# CPU.net
KiCad netlist of a schematic drawn in Altium Designer
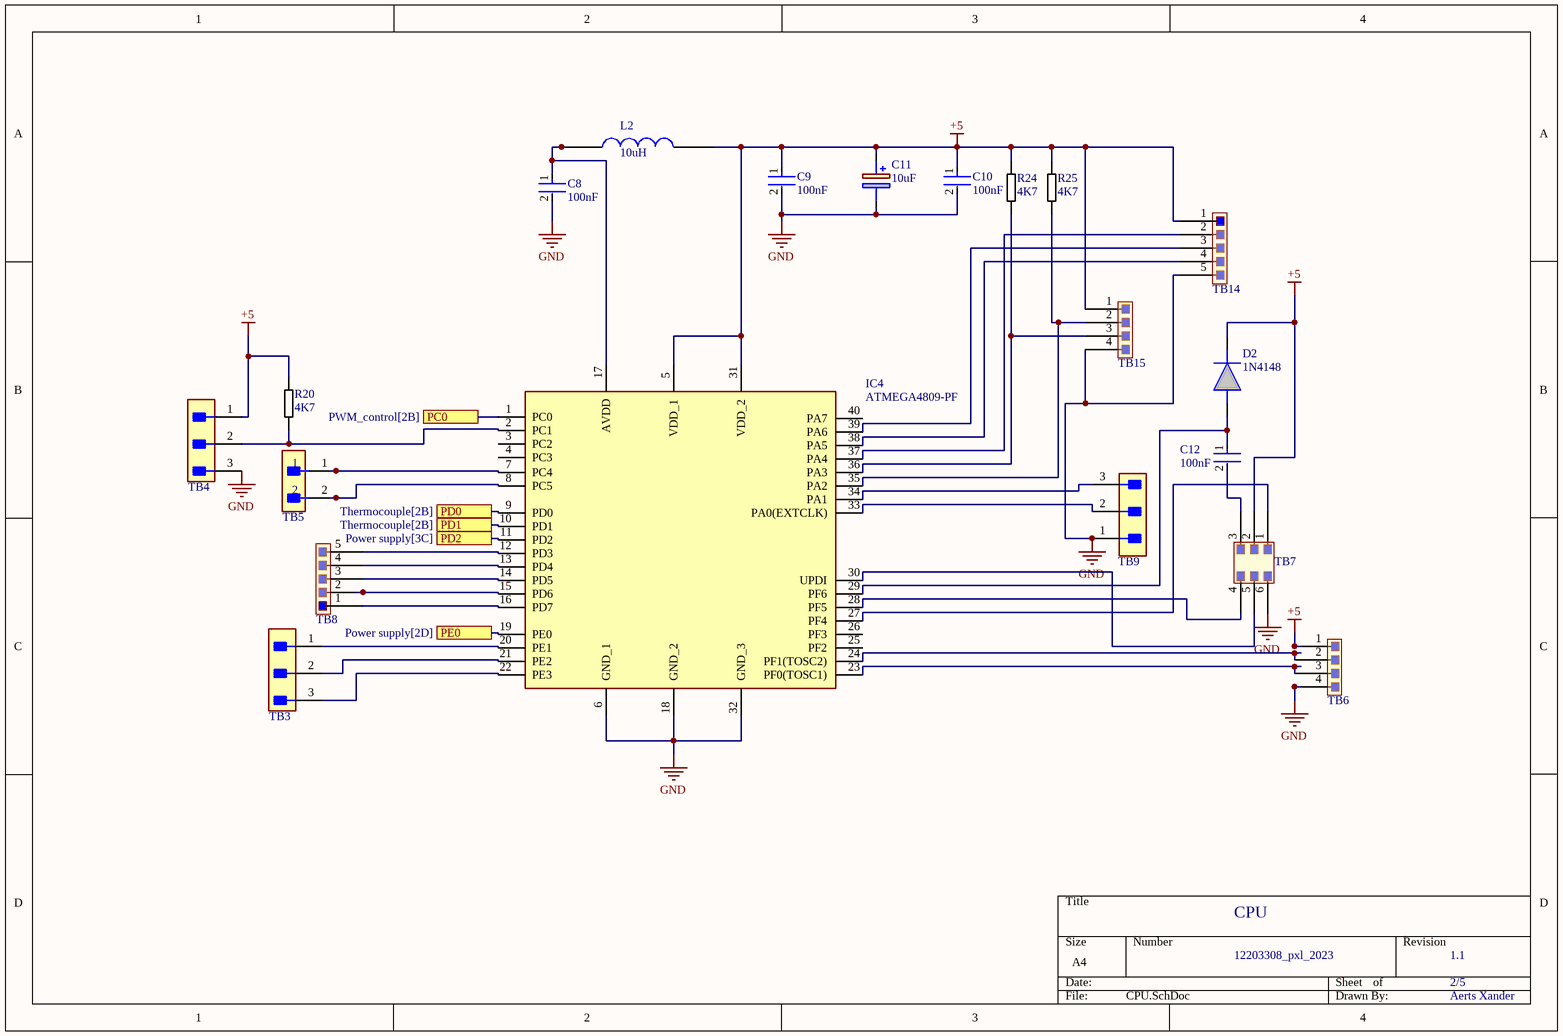
[diagram p0: CPU.SchDoc]

(export (version "E")
  (design (tool "Eeschema 10.0.6"))
  (components
    (comp (ref "C8")
      (value "100nF")
      (footprint "0805")
      (description "CAP CER 10000PF 50V X7R 0603")
      (fields (field (name "TOLERANCE") "0.1") (field (name "MANUFACTURER PART NUMBER") "CC0603KRX7R9BB103"))
      (libsource (lib "soldeerstation") (part "Capacitor 0805"))
    )
    (comp (ref "C9")
      (value "100nF")
      (footprint "0805")
      (description "CAP CER 10000PF 50V X7R 0603")
      (fields (field (name "TOLERANCE") "0.1") (field (name "MANUFACTURER PART NUMBER") "CC0603KRX7R9BB103"))
      (libsource (lib "soldeerstation") (part "Capacitor 0805"))
    )
    (comp (ref "C10")
      (value "100nF")
      (footprint "0805")
      (description "CAP CER 10000PF 50V X7R 0603")
      (fields (field (name "TOLERANCE") "0.1") (field (name "MANUFACTURER PART NUMBER") "CC0603KRX7R9BB103"))
      (libsource (lib "soldeerstation") (part "Capacitor 0805"))
    )
    (comp (ref "C11")
      (value "10uF")
      (footprint "10uF tht")
      (libsource (lib "soldeerstation") (part "10uF tht"))
    )
    (comp (ref "C12")
      (value "100nF")
      (footprint "0805")
      (description "CAP CER 10000PF 50V X7R 0603")
      (fields (field (name "TOLERANCE") "0.1") (field (name "MANUFACTURER PART NUMBER") "CC0603KRX7R9BB103"))
      (libsource (lib "soldeerstation") (part "Capacitor 0805"))
    )
    (comp (ref "D2")
      (value "1N4148")
      (footprint "1n4148")
      (description "Small Signal Diode, 100V 0.3A 2-Pin DO35")
      (fields (field (name "MOUSER PART NUMBER") "512-1N4148"))
      (libsource (lib "soldeerstation") (part "1N4148"))
    )
    (comp (ref "IC4")
      (value "ATMEGA4809-PF")
      (footprint "ATMEGA4809-PF")
      (description "Integrated Circuit")
      (fields (field (name "MOUSER PART NUMBER") "556-ATMEGA4809-PF"))
      (libsource (lib "soldeerstation") (part "ATMEGA4809-PF"))
    )
    (comp (ref "L2")
      (value "10uH")
      (footprint "10uH tht")
      (libsource (lib "soldeerstation") (part "10uH tht"))
    )
    (comp (ref "R20")
      (value "4K7")
      (footprint "0805")
      (fields (field (name "MANUFACTURER") "Vishay Dale") (field (name "PART NUMBER") "CRCW08050000Z0EA"))
      (libsource (lib "soldeerstation") (part "resistor"))
    )
    (comp (ref "R24")
      (value "4K7")
      (footprint "0805")
      (fields (field (name "MANUFACTURER") "Vishay Dale") (field (name "PART NUMBER") "CRCW08050000Z0EA"))
      (libsource (lib "soldeerstation") (part "resistor"))
    )
    (comp (ref "R25")
      (value "4K7")
      (footprint "0805")
      (fields (field (name "MANUFACTURER") "Vishay Dale") (field (name "PART NUMBER") "CRCW08050000Z0EA"))
      (libsource (lib "soldeerstation") (part "resistor"))
    )
    (comp (ref "TB3")
      (value "87224-3")
      (footprint "3x1 header tht")
      (description "CONN HEADER VERT 3POS 2.54MM")
      (libsource (lib "") (part "3x1 header tht_1"))
    )
    (comp (ref "TB4")
      (value "87224-3")
      (footprint "3x1 header tht")
      (description "CONN HEADER VERT 3POS 2.54MM")
      (libsource (lib "") (part "3x1 header tht_1"))
    )
    (comp (ref "TB5")
      (value "TSW-102-07-L-S")
      (footprint "2x1 header tht")
      (description "CONN HEADER VERT 2POS 2.54MM")
      (libsource (lib "soldeerstation") (part "2x1 header tht"))
    )
    (comp (ref "TB6")
      (value "4x1 header tht")
      (footprint "4x1 header tht")
      (libsource (lib "soldeerstation") (part "4x1 header tht"))
    )
    (comp (ref "TB7")
      (value "6x2 header tht")
      (footprint "6x2 header tht")
      (libsource (lib "soldeerstation") (part "6x2 header tht"))
    )
    (comp (ref "TB8")
      (value "5x1 header tht")
      (footprint "5x1 header tht")
      (libsource (lib "") (part "5x1 header tht_1"))
    )
    (comp (ref "TB9")
      (value "87224-3")
      (footprint "3x1 header tht")
      (description "CONN HEADER VERT 3POS 2.54MM")
      (libsource (lib "soldeerstation") (part "3x1 header tht"))
    )
    (comp (ref "TB14")
      (value "5x1 header tht")
      (footprint "5x1 header tht")
      (libsource (lib "soldeerstation") (part "5x1 header tht"))
    )
    (comp (ref "TB15")
      (value "4x1 header tht")
      (footprint "4x1 header tht")
      (libsource (lib "soldeerstation") (part "4x1 header tht"))
    )
  )
  (nets
    (net (code "1") (name "+5") (class "Default")
      (node (ref "C10") (pin "1") (pinfunction "1_1") (pintype "passive"))
      (node (ref "C11") (pin "1") (pinfunction "+_1") (pintype "passive"))
      (node (ref "C9") (pin "1") (pinfunction "1_1") (pintype "passive"))
      (node (ref "D2") (pin "1") (pinfunction "K_1") (pintype "passive"))
      (node (ref "IC4") (pin "31") (pinfunction "VDD_2_31") (pintype "passive"))
      (node (ref "IC4") (pin "5") (pinfunction "VDD_1_5") (pintype "passive"))
      (node (ref "L2") (pin "2") (pinfunction "32_2") (pintype "passive"))
      (node (ref "R20") (pin "2") (pinfunction "2_2") (pintype "passive"))
      (node (ref "R24") (pin "2") (pinfunction "2_2") (pintype "passive"))
      (node (ref "R25") (pin "2") (pinfunction "2_2") (pintype "passive"))
      (node (ref "TB14") (pin "1") (pinfunction "20_1") (pintype "passive"))
      (node (ref "TB15") (pin "1") (pinfunction "16_1") (pintype "passive"))
      (node (ref "TB4") (pin "1") (pinfunction "1_1") (pintype "passive"))
      (node (ref "TB6") (pin "1") (pinfunction "16_1") (pintype "passive"))
      (node (ref "TB7") (pin "2") (pinfunction "22_2") (pintype "passive"))
    )
    (net (code "2") (name "/PC0") (class "Default")
      (node (ref "IC4") (pin "1") (pinfunction "PC0_1") (pintype "passive"))
    )
    (net (code "3") (name "/PD0") (class "Default")
      (node (ref "IC4") (pin "9") (pinfunction "PD0_9") (pintype "passive"))
    )
    (net (code "4") (name "/PD1") (class "Default")
      (node (ref "IC4") (pin "10") (pinfunction "PD1_10") (pintype "passive"))
    )
    (net (code "5") (name "/PD2") (class "Default")
      (node (ref "IC4") (pin "11") (pinfunction "PD2_11") (pintype "passive"))
    )
    (net (code "6") (name "/PE0") (class "Default")
      (node (ref "IC4") (pin "19") (pinfunction "PE0_19") (pintype "passive"))
    )
    (net (code "7") (name "GND") (class "Default")
      (node (ref "C10") (pin "2") (pinfunction "2_2") (pintype "passive"))
      (node (ref "C11") (pin "2") (pinfunction "-_2") (pintype "passive"))
      (node (ref "C8") (pin "2") (pinfunction "2_2") (pintype "passive"))
      (node (ref "C9") (pin "2") (pinfunction "2_2") (pintype "passive"))
      (node (ref "IC4") (pin "18") (pinfunction "GND_2_18") (pintype "passive"))
      (node (ref "IC4") (pin "32") (pinfunction "GND_3_32") (pintype "passive"))
      (node (ref "IC4") (pin "6") (pinfunction "GND_1_6") (pintype "passive"))
      (node (ref "TB14") (pin "5") (pinfunction "19_5") (pintype "passive"))
      (node (ref "TB15") (pin "4") (pinfunction "19_4") (pintype "passive"))
      (node (ref "TB4") (pin "3") (pinfunction "3_3") (pintype "passive"))
      (node (ref "TB6") (pin "4") (pinfunction "19_4") (pintype "passive"))
      (node (ref "TB7") (pin "6") (pinfunction "24_6") (pintype "passive"))
      (node (ref "TB9") (pin "1") (pinfunction "1_1") (pintype "passive"))
    )
    (net (code "8") (name "Net-(D2-A)") (class "Default")
      (node (ref "C12") (pin "1") (pinfunction "1_1") (pintype "passive"))
      (node (ref "D2") (pin "2") (pinfunction "A_2") (pintype "passive"))
      (node (ref "IC4") (pin "29") (pinfunction "PF6_29") (pintype "passive"))
    )
    (net (code "9") (name "Net-(IC4-AVDD)") (class "Default")
      (node (ref "C8") (pin "1") (pinfunction "1_1") (pintype "passive"))
      (node (ref "IC4") (pin "17") (pinfunction "AVDD_17") (pintype "passive"))
      (node (ref "L2") (pin "1") (pinfunction "31_1") (pintype "passive"))
    )
    (net (code "10") (name "Net-(IC4-PA0(EXTCLK))") (class "Default")
      (node (ref "IC4") (pin "33") (pinfunction "PA0(EXTCLK)_33") (pintype "passive"))
      (node (ref "TB9") (pin "2") (pinfunction "2_2") (pintype "passive"))
    )
    (net (code "11") (name "Net-(IC4-PA1)") (class "Default")
      (node (ref "IC4") (pin "34") (pinfunction "PA1_34") (pintype "passive"))
      (node (ref "TB9") (pin "3") (pinfunction "3_3") (pintype "passive"))
    )
    (net (code "12") (name "Net-(IC4-PA2)") (class "Default")
      (node (ref "IC4") (pin "35") (pinfunction "PA2_35") (pintype "passive"))
      (node (ref "R25") (pin "1") (pinfunction "1_1") (pintype "passive"))
      (node (ref "TB15") (pin "2") (pinfunction "17_2") (pintype "passive"))
    )
    (net (code "13") (name "Net-(IC4-PA3)") (class "Default")
      (node (ref "IC4") (pin "36") (pinfunction "PA3_36") (pintype "passive"))
      (node (ref "R24") (pin "1") (pinfunction "1_1") (pintype "passive"))
      (node (ref "TB15") (pin "3") (pinfunction "18_3") (pintype "passive"))
    )
    (net (code "14") (name "Net-(IC4-PA4)") (class "Default")
      (node (ref "IC4") (pin "37") (pinfunction "PA4_37") (pintype "passive"))
      (node (ref "TB14") (pin "2") (pinfunction "16_2") (pintype "passive"))
    )
    (net (code "15") (name "Net-(IC4-PA5)") (class "Default")
      (node (ref "IC4") (pin "38") (pinfunction "PA5_38") (pintype "passive"))
      (node (ref "TB14") (pin "4") (pinfunction "18_4") (pintype "passive"))
    )
    (net (code "16") (name "Net-(IC4-PA6)") (class "Default")
      (node (ref "IC4") (pin "39") (pinfunction "PA6_39") (pintype "passive"))
      (node (ref "TB14") (pin "3") (pinfunction "17_3") (pintype "passive"))
    )
    (net (code "17") (name "Net-(IC4-PC1)") (class "Default")
      (node (ref "IC4") (pin "2") (pinfunction "PC1_2") (pintype "passive"))
      (node (ref "R20") (pin "1") (pinfunction "1_1") (pintype "passive"))
      (node (ref "TB4") (pin "2") (pinfunction "2_2") (pintype "passive"))
    )
    (net (code "18") (name "Net-(IC4-PC4)") (class "Default")
      (node (ref "IC4") (pin "7") (pinfunction "PC4_7") (pintype "passive"))
      (node (ref "TB5") (pin "1") (pinfunction "1_1") (pintype "passive"))
    )
    (net (code "19") (name "Net-(IC4-PC5)") (class "Default")
      (node (ref "IC4") (pin "8") (pinfunction "PC5_8") (pintype "passive"))
      (node (ref "TB5") (pin "2") (pinfunction "2_2") (pintype "passive"))
    )
    (net (code "20") (name "Net-(IC4-PD3)") (class "Default")
      (node (ref "IC4") (pin "12") (pinfunction "PD3_12") (pintype "passive"))
      (node (ref "TB8") (pin "5") (pinfunction "19_5") (pintype "passive"))
    )
    (net (code "21") (name "Net-(IC4-PD4)") (class "Default")
      (node (ref "IC4") (pin "13") (pinfunction "PD4_13") (pintype "passive"))
      (node (ref "TB8") (pin "4") (pinfunction "18_4") (pintype "passive"))
    )
    (net (code "22") (name "Net-(IC4-PD5)") (class "Default")
      (node (ref "IC4") (pin "14") (pinfunction "PD5_14") (pintype "passive"))
      (node (ref "TB8") (pin "3") (pinfunction "17_3") (pintype "passive"))
    )
    (net (code "23") (name "Net-(IC4-PD6)") (class "Default")
      (node (ref "IC4") (pin "15") (pinfunction "PD6_15") (pintype "passive"))
      (node (ref "TB8") (pin "2") (pinfunction "16_2") (pintype "passive"))
    )
    (net (code "24") (name "Net-(IC4-PD7)") (class "Default")
      (node (ref "IC4") (pin "16") (pinfunction "PD7_16") (pintype "passive"))
      (node (ref "TB8") (pin "1") (pinfunction "20_1") (pintype "passive"))
    )
    (net (code "25") (name "Net-(IC4-PE1)") (class "Default")
      (node (ref "IC4") (pin "20") (pinfunction "PE1_20") (pintype "passive"))
      (node (ref "TB3") (pin "1") (pinfunction "1_1") (pintype "passive"))
    )
    (net (code "26") (name "Net-(IC4-PE2)") (class "Default")
      (node (ref "IC4") (pin "21") (pinfunction "PE2_21") (pintype "passive"))
      (node (ref "TB3") (pin "2") (pinfunction "2_2") (pintype "passive"))
    )
    (net (code "27") (name "Net-(IC4-PE3)") (class "Default")
      (node (ref "IC4") (pin "22") (pinfunction "PE3_22") (pintype "passive"))
      (node (ref "TB3") (pin "3") (pinfunction "3_3") (pintype "passive"))
    )
    (net (code "28") (name "Net-(IC4-PF0(TOSC1))") (class "Default")
      (node (ref "IC4") (pin "23") (pinfunction "PF0(TOSC1)_23") (pintype "passive"))
      (node (ref "TB6") (pin "3") (pinfunction "18_3") (pintype "passive"))
    )
    (net (code "29") (name "Net-(IC4-PF1(TOSC2))") (class "Default")
      (node (ref "IC4") (pin "24") (pinfunction "PF1(TOSC2)_24") (pintype "passive"))
      (node (ref "TB6") (pin "2") (pinfunction "17_2") (pintype "passive"))
    )
    (net (code "30") (name "Net-(IC4-PF4)") (class "Default")
      (node (ref "IC4") (pin "27") (pinfunction "PF4_27") (pintype "passive"))
      (node (ref "TB7") (pin "1") (pinfunction "21_1") (pintype "passive"))
    )
    (net (code "31") (name "Net-(IC4-PF5)") (class "Default")
      (node (ref "IC4") (pin "28") (pinfunction "PF5_28") (pintype "passive"))
      (node (ref "TB7") (pin "4") (pinfunction "26_4") (pintype "passive"))
    )
    (net (code "32") (name "Net-(IC4-UPDI)") (class "Default")
      (node (ref "IC4") (pin "30") (pinfunction "UPDI_30") (pintype "passive"))
      (node (ref "TB7") (pin "5") (pinfunction "25_5") (pintype "passive"))
    )
    (net (code "33") (name "Net-(TB7-23)") (class "Default")
      (node (ref "C12") (pin "2") (pinfunction "2_2") (pintype "passive"))
      (node (ref "TB7") (pin "3") (pinfunction "23_3") (pintype "passive"))
    )
    (net (code "34") (name "unconnected-(IC4-PA7-Pad40)") (class "Default")
      (node (ref "IC4") (pin "40") (pinfunction "PA7_40") (pintype "passive"))
    )
    (net (code "35") (name "unconnected-(IC4-PC2-Pad3)") (class "Default")
      (node (ref "IC4") (pin "3") (pinfunction "PC2_3") (pintype "passive"))
    )
    (net (code "36") (name "unconnected-(IC4-PC3-Pad4)") (class "Default")
      (node (ref "IC4") (pin "4") (pinfunction "PC3_4") (pintype "passive"))
    )
    (net (code "37") (name "unconnected-(IC4-PF2-Pad25)") (class "Default")
      (node (ref "IC4") (pin "25") (pinfunction "PF2_25") (pintype "passive"))
    )
    (net (code "38") (name "unconnected-(IC4-PF3-Pad26)") (class "Default")
      (node (ref "IC4") (pin "26") (pinfunction "PF3_26") (pintype "passive"))
    )
  )
)
